# ESP32-S3.net
KiCad netlist of a schematic drawn in Altium Designer
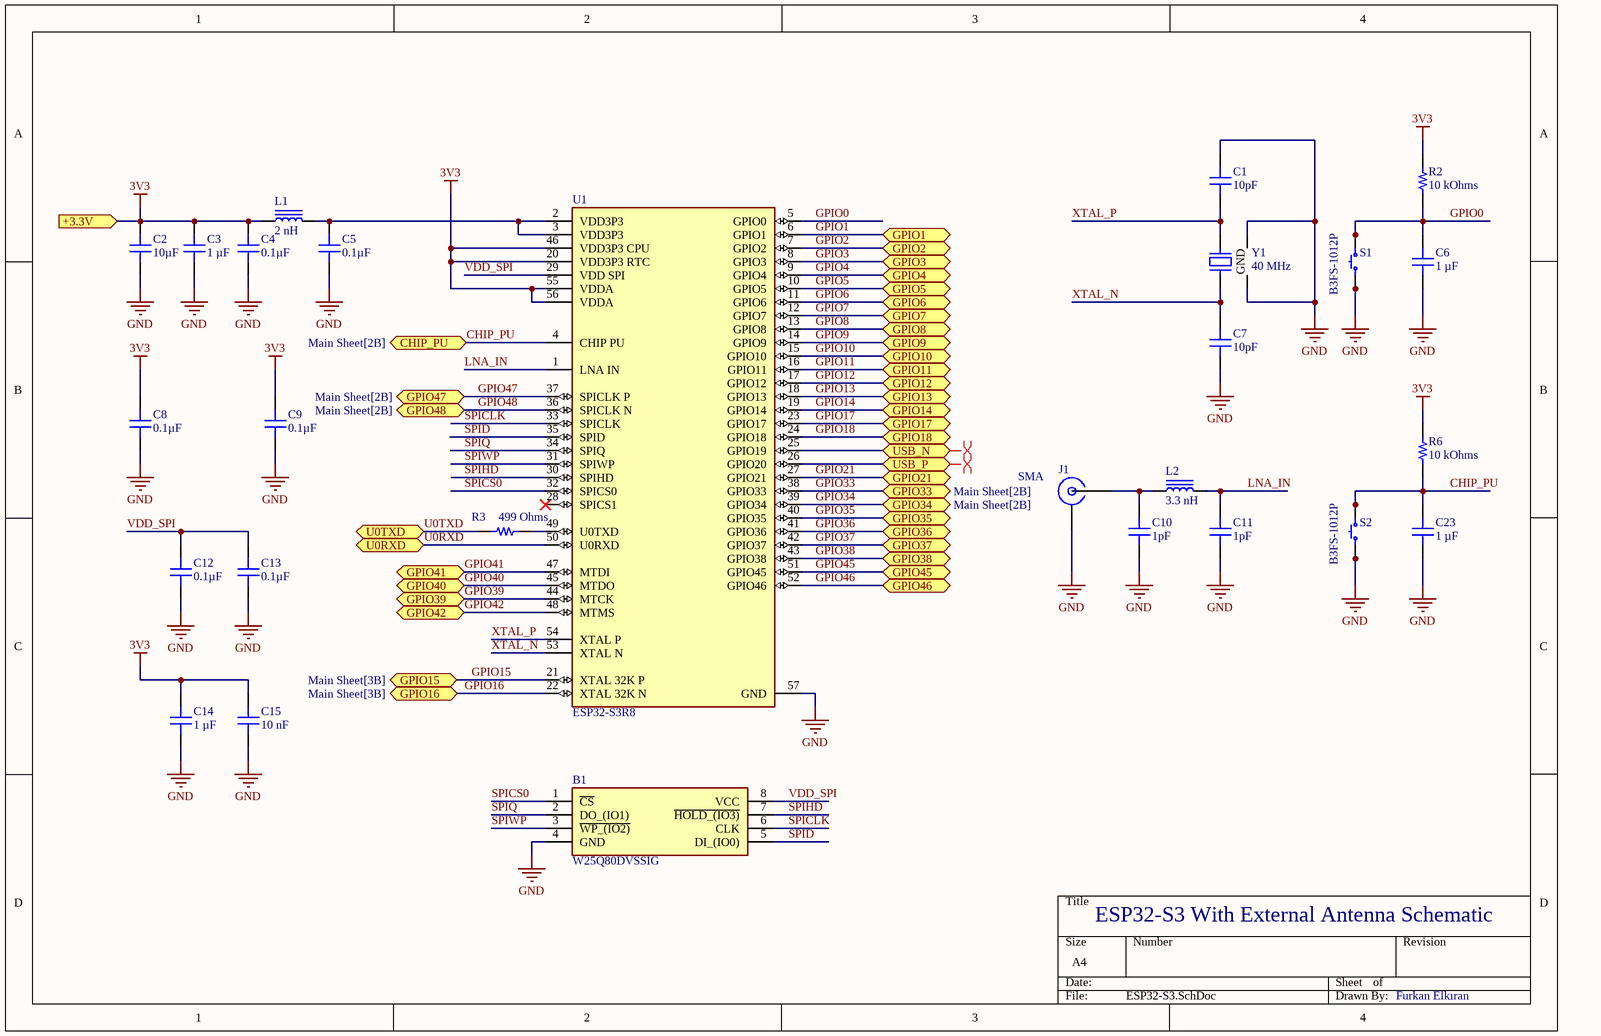
[diagram p0: ESP32-S3.SchDoc]

(export (version "E")
  (design (tool "Eeschema 10.0.6"))
  (components
    (comp (ref "B1")
      (value "W25Q80DVSSIG")
      (footprint "SOIC127P790X216-8N")
      (description "8Mb Serial NOR Flash 104MHz SOP8")
      (fields (field (name "MOUSER PART NUMBER") "454-W25Q80DVSSIG"))
      (libsource (lib "W25Q80DVSSIG") (part "W25Q80DVSSIG"))
    )
    (comp (ref "C1")
      (value "10pF")
      (footprint "CAP 0402_1005")
      (description "CAP CER 10PF 16V NP0 0402")
      (fields
        (field (name "PART NUMBER") "0402YA100KAT2A")
        (field (name "CAPACITANCE") "10pF")
        (field (name "MANUFACTURER") "AVX Corporation")
      )
      (libsource (lib "Celestial Altium Library - altium_library") (part "Capacitor"))
    )
    (comp (ref "C2")
      (value "10µF")
      (footprint "CAP 0402_1005")
      (description "CAP CER 10UF 10V X5R 0402")
      (fields
        (field (name "PART NUMBER") "0402ZD106MAT2A")
        (field (name "CAPACITANCE") "10µF")
        (field (name "MANUFACTURER") "AVX Corporation")
      )
      (libsource (lib "Celestial Altium Library - altium_library") (part "Capacitor"))
    )
    (comp (ref "C3")
      (value "1 µF")
      (footprint "CAP 0402_1005")
      (description "CAP0402 X7R 1UF 10% 10V")
      (fields
        (field (name "PART NUMBER") "GMC04X7R105K10NT")
        (field (name "CAPACITANCE") "1 µF")
        (field (name "MANUFACTURER") "Cal-Chip Electronics, Inc.")
      )
      (libsource (lib "Celestial Altium Library - altium_library") (part "Capacitor"))
    )
    (comp (ref "C4")
      (value "0.1µF")
      (footprint "CAP 0402_1005")
      (description "CAP CER 0.1UF 16V X5R 0402")
      (fields
        (field (name "PART NUMBER") "0402YD104JAT2A")
        (field (name "CAPACITANCE") "0.1µF")
        (field (name "MANUFACTURER") "AVX Corporation")
      )
      (libsource (lib "Celestial Altium Library - altium_library") (part "Capacitor"))
    )
    (comp (ref "C5")
      (value "0.1µF")
      (footprint "CAP 0402_1005")
      (description "CAP CER 0.1UF 16V X5R 0402")
      (fields
        (field (name "PART NUMBER") "0402YD104JAT2A")
        (field (name "CAPACITANCE") "0.1µF")
        (field (name "MANUFACTURER") "AVX Corporation")
      )
      (libsource (lib "Celestial Altium Library - altium_library") (part "Capacitor"))
    )
    (comp (ref "C6")
      (value "1 µF")
      (footprint "CAP 0402_1005")
      (description "CAP0402 X7R 1UF 10% 10V")
      (fields
        (field (name "PART NUMBER") "GMC04X7R105K10NT")
        (field (name "CAPACITANCE") "1 µF")
        (field (name "MANUFACTURER") "Cal-Chip Electronics, Inc.")
      )
      (libsource (lib "Celestial Altium Library - altium_library") (part "Capacitor"))
    )
    (comp (ref "C7")
      (value "10pF")
      (footprint "CAP 0402_1005")
      (description "CAP CER 10PF 16V NP0 0402")
      (fields
        (field (name "PART NUMBER") "0402YA100KAT2A")
        (field (name "CAPACITANCE") "10pF")
        (field (name "MANUFACTURER") "AVX Corporation")
      )
      (libsource (lib "Celestial Altium Library - altium_library") (part "Capacitor"))
    )
    (comp (ref "C8")
      (value "0.1µF")
      (footprint "CAP 0402_1005")
      (description "CAP CER 0.1UF 16V X5R 0402")
      (fields
        (field (name "PART NUMBER") "0402YD104JAT2A")
        (field (name "CAPACITANCE") "0.1µF")
        (field (name "MANUFACTURER") "AVX Corporation")
      )
      (libsource (lib "Celestial Altium Library - altium_library") (part "Capacitor"))
    )
    (comp (ref "C9")
      (value "0.1µF")
      (footprint "CAP 0402_1005")
      (description "CAP CER 0.1UF 16V X5R 0402")
      (fields
        (field (name "PART NUMBER") "0402YD104JAT2A")
        (field (name "CAPACITANCE") "0.1µF")
        (field (name "MANUFACTURER") "AVX Corporation")
      )
      (libsource (lib "Celestial Altium Library - altium_library") (part "Capacitor"))
    )
    (comp (ref "C10")
      (value "1pF")
      (footprint "CAP 0402_1005")
      (description "CAP CER 1PF 25V NP0 0402")
      (fields
        (field (name "PART NUMBER") "04023A1R0BAT2A")
        (field (name "CAPACITANCE") "1pF")
        (field (name "MANUFACTURER") "AVX Corporation")
      )
      (libsource (lib "Celestial Altium Library - altium_library") (part "Capacitor"))
    )
    (comp (ref "C11")
      (value "1pF")
      (footprint "CAP 0402_1005")
      (description "CAP CER 1PF 25V NP0 0402")
      (fields
        (field (name "PART NUMBER") "04023A1R0BAT2A")
        (field (name "CAPACITANCE") "1pF")
        (field (name "MANUFACTURER") "AVX Corporation")
      )
      (libsource (lib "Celestial Altium Library - altium_library") (part "Capacitor"))
    )
    (comp (ref "C12")
      (value "0.1µF")
      (footprint "CAP 0402_1005")
      (description "CAP CER 0.1UF 16V X5R 0402")
      (fields
        (field (name "PART NUMBER") "0402YD104JAT2A")
        (field (name "CAPACITANCE") "0.1µF")
        (field (name "MANUFACTURER") "AVX Corporation")
      )
      (libsource (lib "Celestial Altium Library - altium_library") (part "Capacitor"))
    )
    (comp (ref "C13")
      (value "0.1µF")
      (footprint "CAP 0402_1005")
      (description "CAP CER 0.1UF 16V X5R 0402")
      (fields
        (field (name "PART NUMBER") "0402YD104JAT2A")
        (field (name "CAPACITANCE") "0.1µF")
        (field (name "MANUFACTURER") "AVX Corporation")
      )
      (libsource (lib "Celestial Altium Library - altium_library") (part "Capacitor"))
    )
    (comp (ref "C14")
      (value "1 µF")
      (footprint "CAP 0402_1005")
      (description "CAP0402 X7R 1UF 10% 10V")
      (fields
        (field (name "PART NUMBER") "GMC04X7R105K10NT")
        (field (name "CAPACITANCE") "1 µF")
        (field (name "MANUFACTURER") "Cal-Chip Electronics, Inc.")
      )
      (libsource (lib "Celestial Altium Library - altium_library") (part "Capacitor"))
    )
    (comp (ref "C15")
      (value "1 µF")
      (footprint "CAP 0402_1005")
      (description "CAP0402 X7R 1UF 10% 10V")
      (fields
        (field (name "PART NUMBER") "GMC04X7R105K10NT")
        (field (name "CAPACITANCE") "10 nF")
        (field (name "MANUFACTURER") "Cal-Chip Electronics, Inc.")
      )
      (libsource (lib "Celestial Altium Library - altium_library") (part "Capacitor"))
    )
    (comp (ref "C23")
      (value "1 µF")
      (footprint "CAP 0402_1005")
      (description "CAP0402 X7R 1UF 10% 10V")
      (fields
        (field (name "PART NUMBER") "GMC04X7R105K10NT")
        (field (name "CAPACITANCE") "1 µF")
        (field (name "MANUFACTURER") "Cal-Chip Electronics, Inc.")
      )
      (libsource (lib "Celestial Altium Library - altium_library") (part "Capacitor"))
    )
    (comp (ref "J1")
      (value "0731000114")
      (footprint "MOLEX SD-73100-0114")
      (description "CONN SMA RCPT R/A 50 OHM PCB")
      (fields (field (name "CONNECTOR STYLE") "SMA") (field (name "MANUFACTURER") "Molex"))
      (libsource (lib "Celestial Altium Library - altium_library") (part "COAXIAL JACK"))
    )
    (comp (ref "L1")
      (value "2 nH")
      (footprint "IND 0402_1005")
      (description "FIXED IND 2.0NH 1A 50 MOHM SMD")
      (fields
        (field (name "PART NUMBER") "MHQ1005075HA2N0STD25")
        (field (name "MANUFACTURER") "TDK Corporation")
      )
      (libsource (lib "Celestial Altium Library - altium_library") (part "Inductor"))
    )
    (comp (ref "L2")
      (value "3.3 nH")
      (footprint "Murata LQG15 0402")
      (description "FIXED IND 3.3NH 800MA 0.125OHM")
      (fields
        (field (name "PART NUMBER") "LQG15HH3N3C02D")
        (field (name "MANUFACTURER") "Murata Electronics")
      )
      (libsource (lib "Celestial Altium Library - altium_library") (part "Inductor"))
    )
    (comp (ref "R2")
      (value "10 kOhms")
      (footprint "RES 0402_1005")
      (description "RES SMD 10K OHM 1% 1/10W 0402")
      (fields
        (field (name "PART NUMBER") "MCS0402MC1002FE000")
        (field (name "MANUFACTURER") "Vishay Beyschlag")
      )
      (libsource (lib "Celestial Altium Library - altium_library") (part "Resistor"))
    )
    (comp (ref "R3")
      (value "499 Ohms")
      (footprint "RES 0402_1005")
      (description "RES 499 OHM 1% 1/16W 0402")
      (fields
        (field (name "PART NUMBER") "RMCF0402FT499R")
        (field (name "MANUFACTURER") "Stackpole Electronics Inc")
      )
      (libsource (lib "Celestial Altium Library - altium_library") (part "Resistor"))
    )
    (comp (ref "R6")
      (value "10 kOhms")
      (footprint "RES 0402_1005")
      (description "RES SMD 10K OHM 1% 1/10W 0402")
      (fields
        (field (name "PART NUMBER") "MCS0402MC1002FE000")
        (field (name "MANUFACTURER") "Vishay Beyschlag")
      )
      (libsource (lib "Celestial Altium Library - altium_library") (part "Resistor"))
    )
    (comp (ref "S1")
      (value "B3FS-1012P")
      (footprint "OMRON B3FS-1012P")
      (description "SWITCH TACTILE SPST-NO 0.05A 24V")
      (fields (field (name "MANUFACTURER") "Omron Electronics Inc-EMC Div"))
      (libsource (lib "Celestial Altium Library - altium_library") (part "SPST-NO 4 PIN"))
    )
    (comp (ref "S2")
      (value "B3FS-1012P")
      (footprint "OMRON B3FS-1012P")
      (description "SWITCH TACTILE SPST-NO 0.05A 24V")
      (fields (field (name "MANUFACTURER") "Omron Electronics Inc-EMC Div"))
      (libsource (lib "Celestial Altium Library - altium_library") (part "SPST-NO 4 PIN"))
    )
    (comp (ref "U1")
      (value "ESP32-S3R8")
      (footprint "FP-ESP32-S3R8-IPC_A")
      (description "ESP32-S3R8 RF System on a Chip - SoC SMD IC, Dual-Core MCU, Wi-Fi 2.4G BLE 5.0 Combo")
      (libsource (lib "Altium Content Vault") (part "a095f160bb9f313373d963ad131b0ed"))
    )
    (comp (ref "Y1")
      (value "40 MHz")
      (footprint "NDK NX3225SA")
      (description "CRYSTAL 40.0000MHZ 10PF SMD")
      (fields
        (field (name "PART NUMBER") "NX3225SA-40M-EXS00A-CS03880")
        (field (name "MANUFACTURER") "NDK America, Inc.")
      )
      (libsource (lib "Celestial Altium Library - altium_library") (part "NDK Crystal NX3225SA"))
    )
  )
  (nets
    (net (code "1") (name "/CHIP_PU") (class "Default")
      (node (ref "C23") (pin "2") (pinfunction "2_2") (pintype "passive"))
      (node (ref "R6") (pin "1") (pinfunction "1_1") (pintype "passive"))
      (node (ref "S2") (pin "3") (pinfunction "3_3") (pintype "passive"))
      (node (ref "S2") (pin "4") (pinfunction "4_4") (pintype "passive"))
      (node (ref "U1") (pin "4") (pinfunction "CHIP_PU_4") (pintype "passive"))
    )
    (net (code "2") (name "/GPIO0") (class "Default")
      (node (ref "C6") (pin "2") (pinfunction "2_2") (pintype "passive"))
      (node (ref "R2") (pin "1") (pinfunction "1_1") (pintype "passive"))
      (node (ref "S1") (pin "3") (pinfunction "3_3") (pintype "passive"))
      (node (ref "S1") (pin "4") (pinfunction "4_4") (pintype "passive"))
      (node (ref "U1") (pin "5") (pinfunction "GPIO0_5") (pintype "bidirectional"))
    )
    (net (code "3") (name "/GPIO1") (class "Default")
      (node (ref "U1") (pin "6") (pinfunction "GPIO1_6") (pintype "bidirectional"))
    )
    (net (code "4") (name "/GPIO2") (class "Default")
      (node (ref "U1") (pin "7") (pinfunction "GPIO2_7") (pintype "bidirectional"))
    )
    (net (code "5") (name "/GPIO3") (class "Default")
      (node (ref "U1") (pin "8") (pinfunction "GPIO3_8") (pintype "bidirectional"))
    )
    (net (code "6") (name "/GPIO4") (class "Default")
      (node (ref "U1") (pin "9") (pinfunction "GPIO4_9") (pintype "bidirectional"))
    )
    (net (code "7") (name "/GPIO5") (class "Default")
      (node (ref "U1") (pin "10") (pinfunction "GPIO5_10") (pintype "bidirectional"))
    )
    (net (code "8") (name "/GPIO6") (class "Default")
      (node (ref "U1") (pin "11") (pinfunction "GPIO6_11") (pintype "bidirectional"))
    )
    (net (code "9") (name "/GPIO7") (class "Default")
      (node (ref "U1") (pin "12") (pinfunction "GPIO7_12") (pintype "bidirectional"))
    )
    (net (code "10") (name "/GPIO8") (class "Default")
      (node (ref "U1") (pin "13") (pinfunction "GPIO8_13") (pintype "bidirectional"))
    )
    (net (code "11") (name "/GPIO9") (class "Default")
      (node (ref "U1") (pin "14") (pinfunction "GPIO9_14") (pintype "bidirectional"))
    )
    (net (code "12") (name "/GPIO10") (class "Default")
      (node (ref "U1") (pin "15") (pinfunction "GPIO10_15") (pintype "bidirectional"))
    )
    (net (code "13") (name "/GPIO11") (class "Default")
      (node (ref "U1") (pin "16") (pinfunction "GPIO11_16") (pintype "bidirectional"))
    )
    (net (code "14") (name "/GPIO12") (class "Default")
      (node (ref "U1") (pin "17") (pinfunction "GPIO12_17") (pintype "bidirectional"))
    )
    (net (code "15") (name "/GPIO13") (class "Default")
      (node (ref "U1") (pin "18") (pinfunction "GPIO13_18") (pintype "bidirectional"))
    )
    (net (code "16") (name "/GPIO14") (class "Default")
      (node (ref "U1") (pin "19") (pinfunction "GPIO14_19") (pintype "bidirectional"))
    )
    (net (code "17") (name "/GPIO15") (class "Default")
      (node (ref "U1") (pin "21") (pinfunction "XTAL_32K_P_21") (pintype "bidirectional"))
    )
    (net (code "18") (name "/GPIO16") (class "Default")
      (node (ref "U1") (pin "22") (pinfunction "XTAL_32K_N_22") (pintype "bidirectional"))
    )
    (net (code "19") (name "/GPIO17") (class "Default")
      (node (ref "U1") (pin "23") (pinfunction "GPIO17_23") (pintype "bidirectional"))
    )
    (net (code "20") (name "/GPIO18") (class "Default")
      (node (ref "U1") (pin "24") (pinfunction "GPIO18_24") (pintype "bidirectional"))
    )
    (net (code "21") (name "/GPIO21") (class "Default")
      (node (ref "U1") (pin "27") (pinfunction "GPIO21_27") (pintype "bidirectional"))
    )
    (net (code "22") (name "/GPIO33") (class "Default")
      (node (ref "U1") (pin "38") (pinfunction "GPIO33_38") (pintype "bidirectional"))
    )
    (net (code "23") (name "/GPIO34") (class "Default")
      (node (ref "U1") (pin "39") (pinfunction "GPIO34_39") (pintype "bidirectional"))
    )
    (net (code "24") (name "/GPIO35") (class "Default")
      (node (ref "U1") (pin "40") (pinfunction "GPIO35_40") (pintype "bidirectional"))
    )
    (net (code "25") (name "/GPIO36") (class "Default")
      (node (ref "U1") (pin "41") (pinfunction "GPIO36_41") (pintype "bidirectional"))
    )
    (net (code "26") (name "/GPIO37") (class "Default")
      (node (ref "U1") (pin "42") (pinfunction "GPIO37_42") (pintype "bidirectional"))
    )
    (net (code "27") (name "/GPIO38") (class "Default")
      (node (ref "U1") (pin "43") (pinfunction "GPIO38_43") (pintype "bidirectional"))
    )
    (net (code "28") (name "/GPIO39") (class "Default")
      (node (ref "U1") (pin "44") (pinfunction "MTCK_44") (pintype "bidirectional"))
    )
    (net (code "29") (name "/GPIO40") (class "Default")
      (node (ref "U1") (pin "45") (pinfunction "MTDO_45") (pintype "bidirectional"))
    )
    (net (code "30") (name "/GPIO41") (class "Default")
      (node (ref "U1") (pin "47") (pinfunction "MTDI_47") (pintype "bidirectional"))
    )
    (net (code "31") (name "/GPIO42") (class "Default")
      (node (ref "U1") (pin "48") (pinfunction "MTMS_48") (pintype "bidirectional"))
    )
    (net (code "32") (name "/GPIO45") (class "Default")
      (node (ref "U1") (pin "51") (pinfunction "GPIO45_51") (pintype "bidirectional"))
    )
    (net (code "33") (name "/GPIO46") (class "Default")
      (node (ref "U1") (pin "52") (pinfunction "GPIO46_52") (pintype "bidirectional"))
    )
    (net (code "34") (name "/GPIO47") (class "Default")
      (node (ref "U1") (pin "37") (pinfunction "SPICLK_P_37") (pintype "bidirectional"))
    )
    (net (code "35") (name "/GPIO48") (class "Default")
      (node (ref "U1") (pin "36") (pinfunction "SPICLK_N_36") (pintype "bidirectional"))
    )
    (net (code "36") (name "/LNA_IN") (class "Default")
      (node (ref "C11") (pin "2") (pinfunction "2_2") (pintype "passive"))
      (node (ref "L2") (pin "2") (pinfunction "2_2") (pintype "passive"))
      (node (ref "U1") (pin "1") (pinfunction "LNA_IN_1") (pintype "passive"))
    )
    (net (code "37") (name "/SPICLK") (class "Default")
      (node (ref "B1") (pin "6") (pinfunction "CLK_6") (pintype "passive"))
      (node (ref "U1") (pin "33") (pinfunction "SPICLK_33") (pintype "bidirectional"))
    )
    (net (code "38") (name "/SPICS0") (class "Default")
      (node (ref "B1") (pin "1") (pinfunction "~{CS}_1") (pintype "passive"))
      (node (ref "U1") (pin "32") (pinfunction "SPICS0_32") (pintype "bidirectional"))
    )
    (net (code "39") (name "/SPID") (class "Default")
      (node (ref "B1") (pin "5") (pinfunction "DI_(IO0)_5") (pintype "passive"))
      (node (ref "U1") (pin "35") (pinfunction "SPID_35") (pintype "bidirectional"))
    )
    (net (code "40") (name "/SPIHD") (class "Default")
      (node (ref "B1") (pin "7") (pinfunction "~{HOLD_(IO3)}_7") (pintype "passive"))
      (node (ref "U1") (pin "30") (pinfunction "SPIHD_30") (pintype "bidirectional"))
    )
    (net (code "41") (name "/SPIQ") (class "Default")
      (node (ref "B1") (pin "2") (pinfunction "DO_(IO1)_2") (pintype "passive"))
      (node (ref "U1") (pin "34") (pinfunction "SPIQ_34") (pintype "bidirectional"))
    )
    (net (code "42") (name "/SPIWP") (class "Default")
      (node (ref "B1") (pin "3") (pinfunction "~{WP_(IO2)}_3") (pintype "passive"))
      (node (ref "U1") (pin "31") (pinfunction "SPIWP_31") (pintype "bidirectional"))
    )
    (net (code "43") (name "/U0RXD") (class "Default")
      (node (ref "U1") (pin "50") (pinfunction "U0RXD_50") (pintype "bidirectional"))
    )
    (net (code "44") (name "/U0TXD") (class "Default")
      (node (ref "R3") (pin "1") (pinfunction "1_1") (pintype "passive"))
    )
    (net (code "45") (name "/USB_N") (class "Default")
      (node (ref "U1") (pin "25") (pinfunction "GPIO19_25") (pintype "bidirectional"))
    )
    (net (code "46") (name "/USB_P") (class "Default")
      (node (ref "U1") (pin "26") (pinfunction "GPIO20_26") (pintype "bidirectional"))
    )
    (net (code "47") (name "/VDD_SPI") (class "Default")
      (node (ref "B1") (pin "8") (pinfunction "VCC_8") (pintype "passive"))
      (node (ref "C12") (pin "2") (pinfunction "2_2") (pintype "passive"))
      (node (ref "C13") (pin "2") (pinfunction "2_2") (pintype "passive"))
      (node (ref "U1") (pin "29") (pinfunction "VDD_SPI_29") (pintype "power_in"))
    )
    (net (code "48") (name "/XTAL_N") (class "Default")
      (node (ref "C7") (pin "2") (pinfunction "2_2") (pintype "passive"))
      (node (ref "U1") (pin "53") (pinfunction "XTAL_N_53") (pintype "passive"))
      (node (ref "Y1") (pin "1") (pinfunction "1_1") (pintype "passive"))
    )
    (net (code "49") (name "/XTAL_P") (class "Default")
      (node (ref "C1") (pin "1") (pinfunction "1_1") (pintype "passive"))
      (node (ref "U1") (pin "54") (pinfunction "XTAL_P_54") (pintype "passive"))
      (node (ref "Y1") (pin "3") (pinfunction "3_3") (pintype "passive"))
    )
    (net (code "50") (name "3V3") (class "Default")
      (node (ref "C14") (pin "2") (pinfunction "2_2") (pintype "passive"))
      (node (ref "C15") (pin "2") (pinfunction "2_2") (pintype "passive"))
      (node (ref "C2") (pin "2") (pinfunction "2_2") (pintype "passive"))
      (node (ref "C3") (pin "2") (pinfunction "2_2") (pintype "passive"))
      (node (ref "C4") (pin "2") (pinfunction "2_2") (pintype "passive"))
      (node (ref "C8") (pin "2") (pinfunction "2_2") (pintype "passive"))
      (node (ref "C9") (pin "2") (pinfunction "2_2") (pintype "passive"))
      (node (ref "L1") (pin "1") (pinfunction "1_1") (pintype "passive"))
      (node (ref "R2") (pin "2") (pinfunction "2_2") (pintype "passive"))
      (node (ref "R6") (pin "2") (pinfunction "2_2") (pintype "passive"))
      (node (ref "U1") (pin "20") (pinfunction "VDD3P3_RTC_20") (pintype "power_in"))
      (node (ref "U1") (pin "46") (pinfunction "VDD3P3_CPU_46") (pintype "power_in"))
      (node (ref "U1") (pin "55") (pinfunction "VDDA_55") (pintype "power_in"))
      (node (ref "U1") (pin "56") (pinfunction "VDDA_56") (pintype "power_in"))
    )
    (net (code "51") (name "GND") (class "Default")
      (node (ref "B1") (pin "4") (pinfunction "GND_4") (pintype "passive"))
      (node (ref "C1") (pin "2") (pinfunction "2_2") (pintype "passive"))
      (node (ref "C10") (pin "1") (pinfunction "1_1") (pintype "passive"))
      (node (ref "C11") (pin "1") (pinfunction "1_1") (pintype "passive"))
      (node (ref "C12") (pin "1") (pinfunction "1_1") (pintype "passive"))
      (node (ref "C13") (pin "1") (pinfunction "1_1") (pintype "passive"))
      (node (ref "C14") (pin "1") (pinfunction "1_1") (pintype "passive"))
      (node (ref "C15") (pin "1") (pinfunction "1_1") (pintype "passive"))
      (node (ref "C2") (pin "1") (pinfunction "1_1") (pintype "passive"))
      (node (ref "C23") (pin "1") (pinfunction "1_1") (pintype "passive"))
      (node (ref "C3") (pin "1") (pinfunction "1_1") (pintype "passive"))
      (node (ref "C4") (pin "1") (pinfunction "1_1") (pintype "passive"))
      (node (ref "C5") (pin "1") (pinfunction "1_1") (pintype "passive"))
      (node (ref "C6") (pin "1") (pinfunction "1_1") (pintype "passive"))
      (node (ref "C7") (pin "1") (pinfunction "1_1") (pintype "passive"))
      (node (ref "C8") (pin "1") (pinfunction "1_1") (pintype "passive"))
      (node (ref "C9") (pin "1") (pinfunction "1_1") (pintype "passive"))
      (node (ref "J1") (pin "G") (pinfunction "GND_G") (pintype "passive"))
      (node (ref "S1") (pin "1") (pinfunction "1_1") (pintype "passive"))
      (node (ref "S1") (pin "2") (pinfunction "2_2") (pintype "passive"))
      (node (ref "S2") (pin "1") (pinfunction "1_1") (pintype "passive"))
      (node (ref "S2") (pin "2") (pinfunction "2_2") (pintype "passive"))
      (node (ref "U1") (pin "57") (pinfunction "GND_57") (pintype "power_in"))
      (node (ref "Y1") (pin "2") (pinfunction "GND_2") (pintype "passive"))
      (node (ref "Y1") (pin "4") (pinfunction "GND_4") (pintype "passive"))
    )
    (net (code "52") (name "Net-(C5-Pad2)") (class "Default")
      (node (ref "C5") (pin "2") (pinfunction "2_2") (pintype "passive"))
      (node (ref "L1") (pin "2") (pinfunction "2_2") (pintype "passive"))
      (node (ref "U1") (pin "2") (pinfunction "VDD3P3_2") (pintype "power_in"))
      (node (ref "U1") (pin "3") (pinfunction "VDD3P3_3") (pintype "power_in"))
    )
    (net (code "53") (name "Net-(J1-SIGNAL)") (class "Default")
      (node (ref "C10") (pin "2") (pinfunction "2_2") (pintype "passive"))
      (node (ref "J1") (pin "S") (pinfunction "SIGNAL_S") (pintype "passive"))
      (node (ref "L2") (pin "1") (pinfunction "1_1") (pintype "passive"))
    )
    (net (code "54") (name "Net-(U1-U0TXD)") (class "Default")
      (node (ref "R3") (pin "2") (pinfunction "2_2") (pintype "passive"))
      (node (ref "U1") (pin "49") (pinfunction "U0TXD_49") (pintype "bidirectional"))
    )
    (net (code "55") (name "unconnected-(U1-SPICS1-Pad28)") (class "Default")
      (node (ref "U1") (pin "28") (pinfunction "SPICS1_28") (pintype "bidirectional+no_connect"))
    )
  )
)
